# 5kW_Sensor.net
KiCad netlist of a schematic drawn in Altium Designer
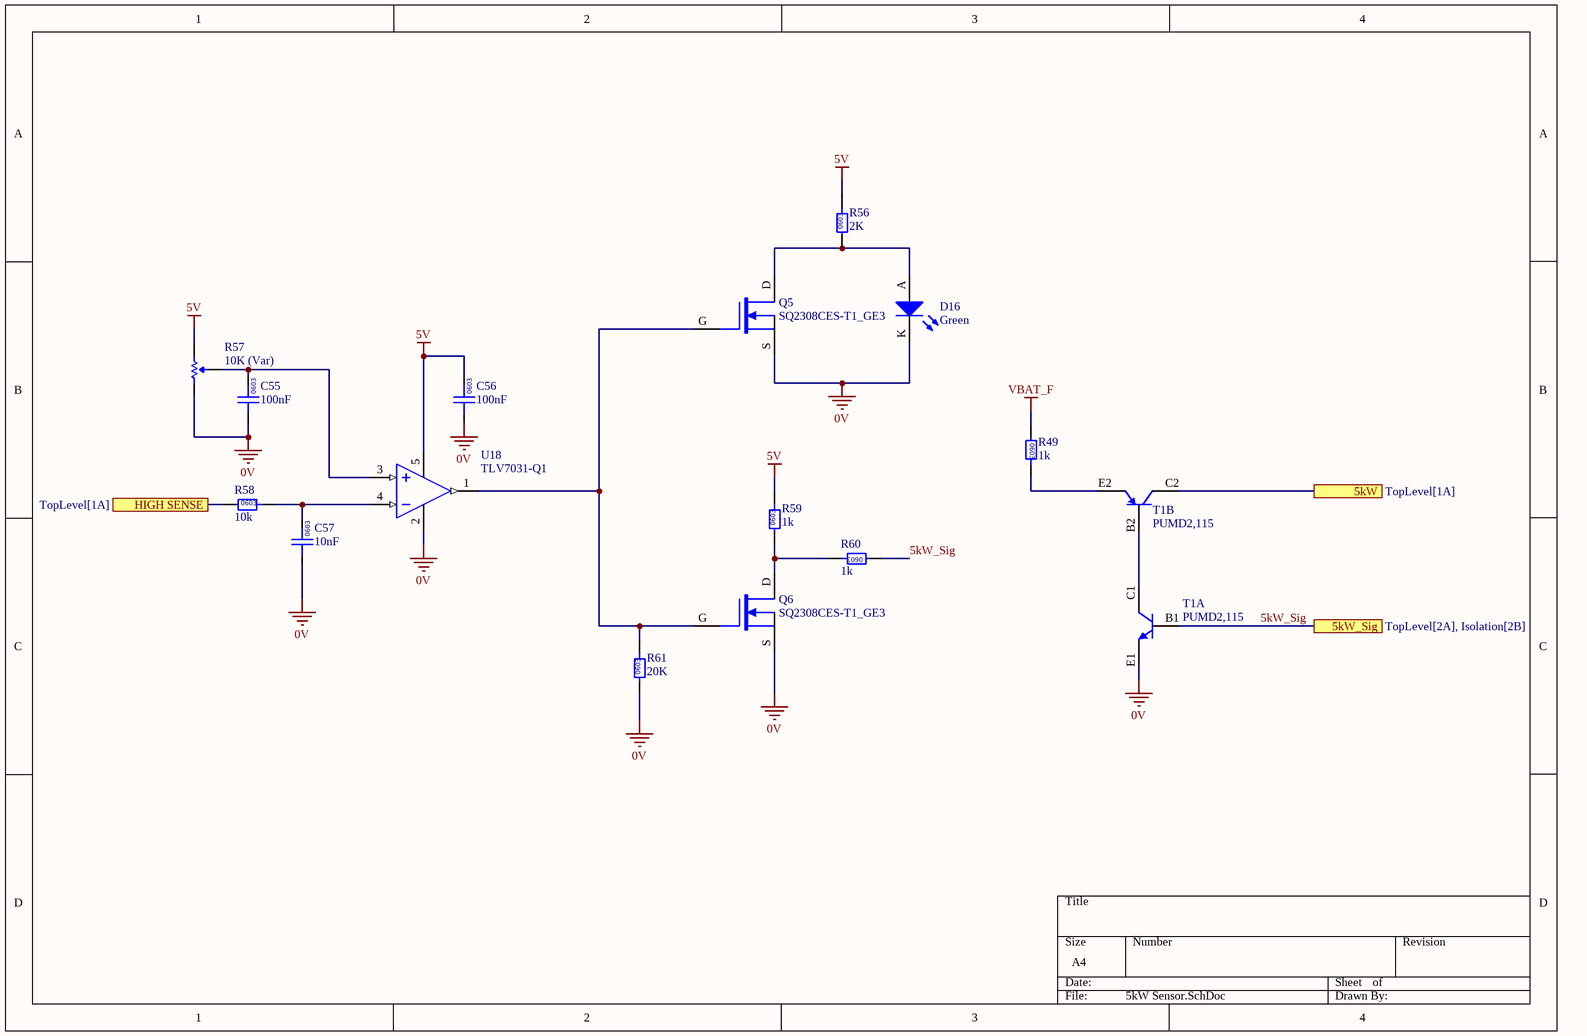
[diagram p0: 5kW Sensor.SchDoc]

(export (version "E")
  (design (tool "Eeschema 10.0.6"))
  (components
    (comp (ref "C55")
      (value "100nF")
      (footprint "0603")
      (fields
        (field (name "PART NUMBER") "GCM188L81H104KA57D")
        (field (name "MANUFACTURER") "muRata")
        (field (name "TOLERANCE") "±10%")
      )
      (libsource (lib "ts_standard_library") (part "Capacitor 0603"))
    )
    (comp (ref "C56")
      (value "100nF")
      (footprint "0603")
      (fields
        (field (name "PART NUMBER") "GCM188L81H104KA57D")
        (field (name "MANUFACTURER") "muRata")
        (field (name "TOLERANCE") "±10%")
      )
      (libsource (lib "ts_standard_library") (part "Capacitor 0603"))
    )
    (comp (ref "C57")
      (value "10nF")
      (footprint "0603")
      (fields
        (field (name "PART NUMBER") "GCM188L81H103KA03D")
        (field (name "MANUFACTURER") "muRata")
        (field (name "TOLERANCE") "±10%")
      )
      (libsource (lib "ts_standard_library") (part "Capacitor 0603"))
    )
    (comp (ref "D16")
      (value "Green")
      (footprint "0805 LED")
      (description "Green LED Indication - Discrete 1.75V 0805 (2012 Metric)")
      (fields (field (name "PART NUMBER") "SML-210FTT86") (field (name "MANUFACTURER") "ROHM Semiconductor"))
      (libsource (lib "ts_standard_library") (part "LED"))
    )
    (comp (ref "Q5")
      (value "SQ2308CES-T1_GE3")
      (footprint "VSHY SOT-23-3")
      (description "MOSFET N-CH 60V 2.3A SOT23")
      (fields
        (field (name "MANUFACTURER") "Vishay Siliconix")
        (field (name "DIGIKEY PART NUMBER") "SQ2308CES-T1_GE3CT-ND")
        (field (name "PUBLISHER") "Altium Limited")
      )
      (libsource (lib "ts_standard_library") (part "MOSFET-N"))
    )
    (comp (ref "Q6")
      (value "SQ2308CES-T1_GE3")
      (footprint "VSHY SOT-23-3")
      (description "MOSFET N-CH 60V 2.3A SOT23")
      (fields
        (field (name "MANUFACTURER") "Vishay Siliconix")
        (field (name "DIGIKEY PART NUMBER") "SQ2308CES-T1_GE3CT-ND")
        (field (name "PUBLISHER") "Altium Limited")
      )
      (libsource (lib "ts_standard_library") (part "MOSFET-N"))
    )
    (comp (ref "R49")
      (value "1k")
      (footprint "0603")
      (fields
        (field (name "PART NUMBER") "RC0603FR-071KL")
        (field (name "MANUFACTURER") "YAGEO")
        (field (name "TOLERANCE") "0.01")
      )
      (libsource (lib "ts_standard_library") (part "Resistor 0603"))
    )
    (comp (ref "R56")
      (value "2K")
      (footprint "0603")
      (fields
        (field (name "PART NUMBER") "RC0603FR-072KL")
        (field (name "MANUFACTURER") "YAGEO")
        (field (name "TOLERANCE") "0.01")
      )
      (libsource (lib "ts_standard_library") (part "Resistor 0603"))
    )
    (comp (ref "R57")
      (value "10K (Var)")
      (footprint "B 3296")
      (fields
        (field (name "PART NUMBER") "3296W-1-103LF")
        (field (name "MANUFACTURER") "Bournes Inc")
        (field (name "TOLERANCE") "0.1")
      )
      (libsource (lib "ts_standard_library") (part "Resistor (Potentiometer)"))
    )
    (comp (ref "R58")
      (value "10k")
      (footprint "0603")
      (fields
        (field (name "PART NUMBER") "RC0603FR-0710KL")
        (field (name "MANUFACTURER") "YAGEO")
        (field (name "TOLERANCE") "0.01")
      )
      (libsource (lib "ts_standard_library") (part "Resistor 0603"))
    )
    (comp (ref "R59")
      (value "1k")
      (footprint "0603")
      (fields
        (field (name "PART NUMBER") "RC0603FR-071KL")
        (field (name "MANUFACTURER") "YAGEO")
        (field (name "TOLERANCE") "0.01")
      )
      (libsource (lib "ts_standard_library") (part "Resistor 0603"))
    )
    (comp (ref "R60")
      (value "1k")
      (footprint "0603")
      (fields
        (field (name "PART NUMBER") "RC0603FR-071KL")
        (field (name "MANUFACTURER") "YAGEO")
        (field (name "TOLERANCE") "0.01")
      )
      (libsource (lib "ts_standard_library") (part "Resistor 0603"))
    )
    (comp (ref "R61")
      (value "20K")
      (footprint "0603")
      (fields
        (field (name "PART NUMBER") "RC0603FR-0720KL")
        (field (name "MANUFACTURER") "YAGEO")
        (field (name "TOLERANCE") "0.01")
      )
      (libsource (lib "ts_standard_library") (part "Resistor 0603"))
    )
    (comp (ref "T1")
      (value "PUMD2,115")
      (footprint "NXP, SOT363")
      (description "Small Signal Bipolar Transistor, 0.1A I(C), 50V V(BR)CEO, 2-Element, NPN and PNP, Silicon")
      (libsource (lib "Team Swinburne") (part "PUMD2,115"))
    )
    (comp (ref "U18")
      (value "TLV7031-Q1")
      (footprint "TI SOT-23-5")
      (fields
        (field (name "MANUFACTURER") "Texas Instruments")
        (field (name "DIGIKEY PART NUMBER") "296-TLV7031QDBVRQ1CT-ND")
      )
      (libsource (lib "ts_standard_library") (part "TLV7031-Q1"))
    )
  )
  (nets
    (net (code "1") (name "/5kW") (class "Default")
      (node (ref "T1") (pin "C2") (pinfunction "C_C2") (pintype "passive"))
    )
    (net (code "2") (name "/5kW_Sig") (class "Default")
      (node (ref "R60") (pin "1") (pinfunction "1_1") (pintype "passive"))
      (node (ref "T1") (pin "B1") (pinfunction "B1_B1") (pintype "passive"))
    )
    (net (code "3") (name "/HIGH SENSE") (class "Default")
      (node (ref "R58") (pin "1") (pinfunction "1_1") (pintype "passive"))
    )
    (net (code "4") (name "0V") (class "Default")
      (node (ref "C55") (pin "1") (pinfunction "1_1") (pintype "passive"))
      (node (ref "C56") (pin "1") (pinfunction "1_1") (pintype "passive"))
      (node (ref "C57") (pin "1") (pinfunction "1_1") (pintype "passive"))
      (node (ref "D16") (pin "K") (pinfunction "K_K") (pintype "passive"))
      (node (ref "Q5") (pin "S") (pinfunction "S_S") (pintype "passive"))
      (node (ref "Q6") (pin "S") (pinfunction "S_S") (pintype "passive"))
      (node (ref "R57") (pin "3") (pinfunction "CW_3") (pintype "passive"))
      (node (ref "R61") (pin "1") (pinfunction "1_1") (pintype "passive"))
      (node (ref "T1") (pin "E1") (pinfunction "E1_E1") (pintype "passive"))
      (node (ref "U18") (pin "2") (pinfunction "V-_2") (pintype "power_in"))
    )
    (net (code "5") (name "5V") (class "Default")
      (node (ref "C56") (pin "2") (pinfunction "2_2") (pintype "passive"))
      (node (ref "R56") (pin "2") (pinfunction "2_2") (pintype "passive"))
      (node (ref "R57") (pin "1") (pinfunction "CCW_1") (pintype "passive"))
      (node (ref "R59") (pin "2") (pinfunction "2_2") (pintype "passive"))
      (node (ref "U18") (pin "5") (pinfunction "Vcc_5") (pintype "power_in"))
    )
    (net (code "6") (name "Net-(D16-PadA)") (class "Default")
      (node (ref "D16") (pin "A") (pinfunction "A_A") (pintype "passive"))
      (node (ref "Q5") (pin "D") (pinfunction "D_D") (pintype "passive"))
      (node (ref "R56") (pin "1") (pinfunction "1_1") (pintype "passive"))
    )
    (net (code "7") (name "Net-(Q6-PadD)") (class "Default")
      (node (ref "Q6") (pin "D") (pinfunction "D_D") (pintype "passive"))
      (node (ref "R59") (pin "1") (pinfunction "1_1") (pintype "passive"))
      (node (ref "R60") (pin "2") (pinfunction "2_2") (pintype "passive"))
    )
    (net (code "8") (name "Net-(R57-Wiper)") (class "Default")
      (node (ref "C55") (pin "2") (pinfunction "2_2") (pintype "passive"))
      (node (ref "R57") (pin "2") (pinfunction "Wiper_2") (pintype "passive"))
      (node (ref "U18") (pin "3") (pinfunction "IN+_3") (pintype "input"))
    )
    (net (code "9") (name "Net-(T1-PadB2)") (class "Default")
      (node (ref "T1") (pin "B2") (pinfunction "B2_B2") (pintype "passive"))
      (node (ref "T1") (pin "C1") (pinfunction "C1_C1") (pintype "passive"))
    )
    (net (code "10") (name "Net-(T1B-E)") (class "Default")
      (node (ref "R49") (pin "2") (pinfunction "2_2") (pintype "passive"))
      (node (ref "T1") (pin "E2") (pinfunction "E_E2") (pintype "passive"))
    )
    (net (code "11") (name "Net-(U18-IN-)") (class "Default")
      (node (ref "C57") (pin "2") (pinfunction "2_2") (pintype "passive"))
      (node (ref "R58") (pin "2") (pinfunction "2_2") (pintype "passive"))
      (node (ref "U18") (pin "4") (pinfunction "IN-_4") (pintype "input"))
    )
    (net (code "12") (name "Net-(U18-OUT)") (class "Default")
      (node (ref "Q5") (pin "G") (pinfunction "G_G") (pintype "passive"))
      (node (ref "Q6") (pin "G") (pinfunction "G_G") (pintype "passive"))
      (node (ref "R61") (pin "2") (pinfunction "2_2") (pintype "passive"))
      (node (ref "U18") (pin "1") (pinfunction "OUT_1") (pintype "output"))
    )
    (net (code "13") (name "VBAT_F") (class "Default")
      (node (ref "R49") (pin "1") (pinfunction "1_1") (pintype "passive"))
    )
  )
)
